# Latching.net
KiCad netlist of a schematic drawn in Altium Designer
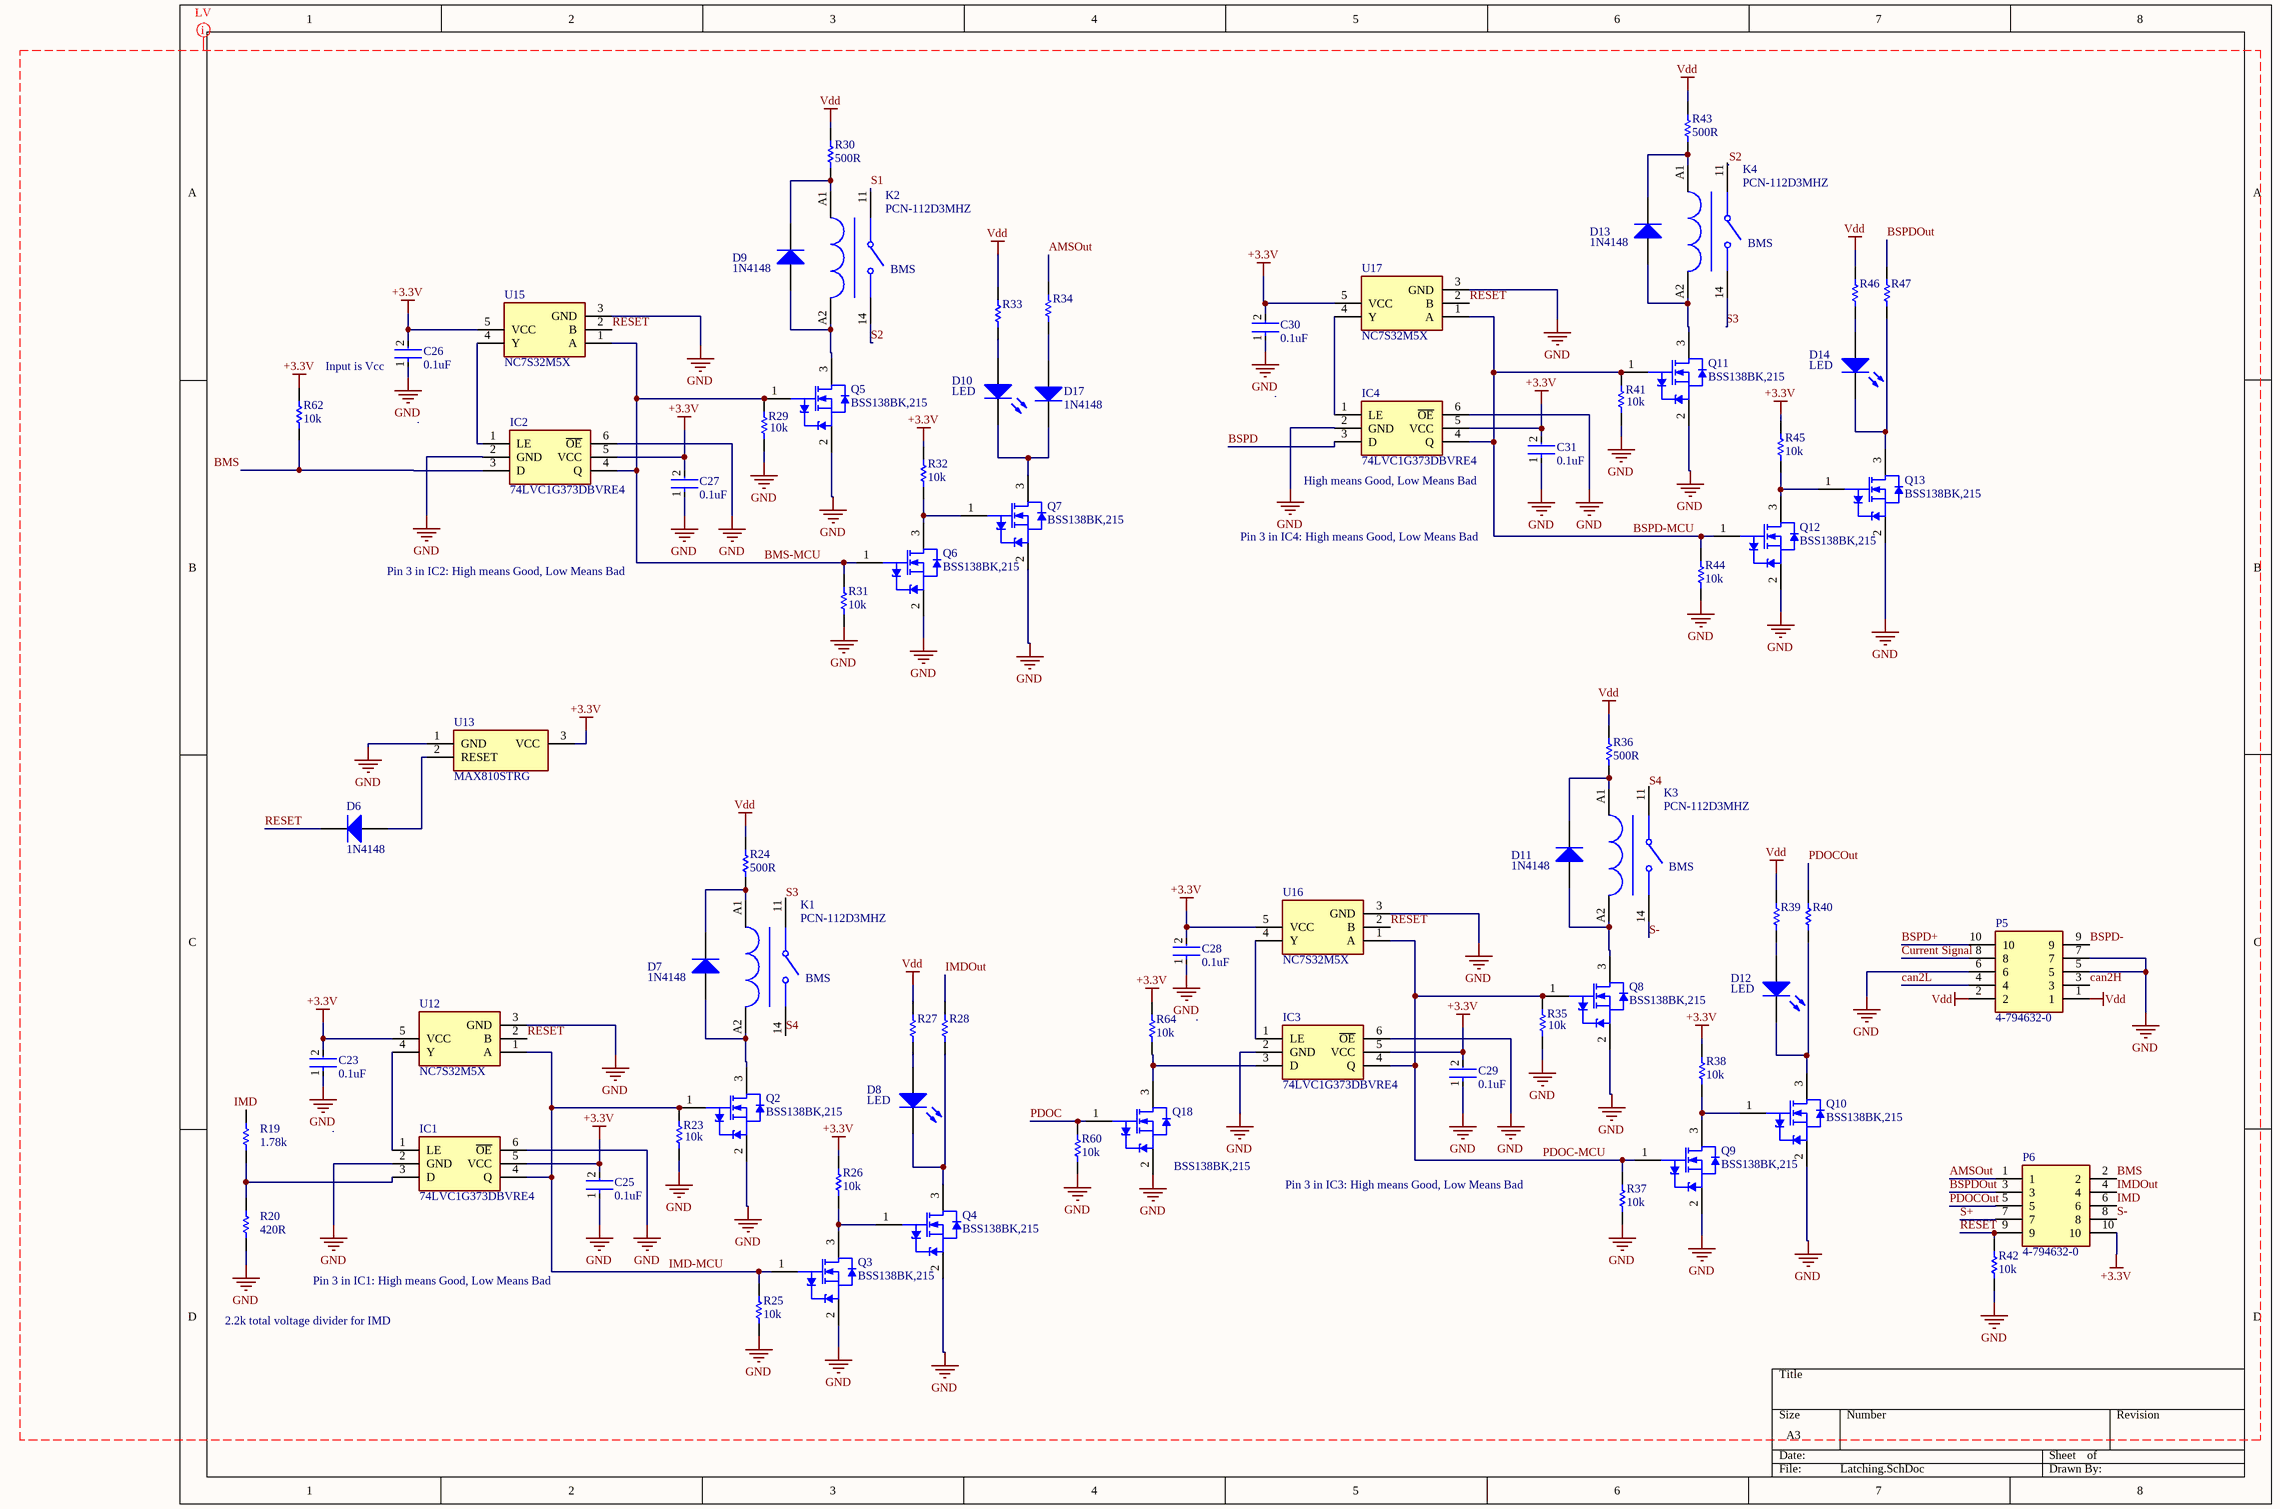
[diagram p0: Latching.SchDoc]

(export (version "E")
  (design (tool "Eeschema 10.0.6"))
  (components
    (comp (ref "C23")
      (value "0.1uF")
      (footprint "FP-C0603-CJ-MFG")
      (description "CAP CER 0.1UF 50V X7R 0603")
      (fields (field (name "MANUFACTURER PART NUMBER") "C0603X104K5RACTU") (field (name "VOLTAGE") "50V"))
      (libsource (lib "Altium Content Vault") (part "11868f565c42a9108669ba33697ecf6"))
    )
    (comp (ref "C25")
      (value "0.1uF")
      (footprint "FP-C0603-CJ-MFG")
      (description "CAP CER 0.1UF 50V X7R 0603")
      (fields (field (name "MANUFACTURER PART NUMBER") "C0603X104K5RACTU") (field (name "VOLTAGE") "50V"))
      (libsource (lib "Altium Content Vault") (part "11868f565c42a9108669ba33697ecf6"))
    )
    (comp (ref "C26")
      (value "0.1uF")
      (footprint "FP-C0603-CJ-MFG")
      (description "CAP CER 0.1UF 50V X7R 0603")
      (fields (field (name "MANUFACTURER PART NUMBER") "C0603X104K5RACTU") (field (name "VOLTAGE") "50V"))
      (libsource (lib "Altium Content Vault") (part "11868f565c42a9108669ba33697ecf6"))
    )
    (comp (ref "C27")
      (value "0.1uF")
      (footprint "FP-C0603-CJ-MFG")
      (description "CAP CER 0.1UF 50V X7R 0603")
      (fields (field (name "MANUFACTURER PART NUMBER") "C0603X104K5RACTU") (field (name "VOLTAGE") "50V"))
      (libsource (lib "Altium Content Vault") (part "11868f565c42a9108669ba33697ecf6"))
    )
    (comp (ref "C28")
      (value "0.1uF")
      (footprint "FP-C0603-CJ-MFG")
      (description "CAP CER 0.1UF 50V X7R 0603")
      (fields (field (name "MANUFACTURER PART NUMBER") "C0603X104K5RACTU") (field (name "VOLTAGE") "50V"))
      (libsource (lib "Altium Content Vault") (part "11868f565c42a9108669ba33697ecf6"))
    )
    (comp (ref "C29")
      (value "0.1uF")
      (footprint "FP-C0603-CJ-MFG")
      (description "CAP CER 0.1UF 50V X7R 0603")
      (fields (field (name "MANUFACTURER PART NUMBER") "C0603X104K5RACTU") (field (name "VOLTAGE") "50V"))
      (libsource (lib "Altium Content Vault") (part "11868f565c42a9108669ba33697ecf6"))
    )
    (comp (ref "C30")
      (value "0.1uF")
      (footprint "FP-C0603-CJ-MFG")
      (description "CAP CER 0.1UF 50V X7R 0603")
      (fields (field (name "MANUFACTURER PART NUMBER") "C0603X104K5RACTU") (field (name "VOLTAGE") "50V"))
      (libsource (lib "Altium Content Vault") (part "11868f565c42a9108669ba33697ecf6"))
    )
    (comp (ref "C31")
      (value "0.1uF")
      (footprint "FP-C0603-CJ-MFG")
      (description "CAP CER 0.1UF 50V X7R 0603")
      (fields (field (name "MANUFACTURER PART NUMBER") "C0603X104K5RACTU") (field (name "VOLTAGE") "50V"))
      (libsource (lib "Altium Content Vault") (part "11868f565c42a9108669ba33697ecf6"))
    )
    (comp (ref "D6")
      (value "1N4148")
      (footprint "DIOD-SOD123-2_V")
      (description "DIODE GEN PURP 100V 300MA SOD123")
      (fields (field (name "VOLTAGE") "100V"))
      (libsource (lib "Diodes") (part "1N4148W-7-F"))
    )
    (comp (ref "D7")
      (value "1N4148")
      (footprint "DIOD-SOD123-2_V")
      (description "DIODE GEN PURP 100V 300MA SOD123")
      (fields (field (name "VOLTAGE") "100V"))
      (libsource (lib "Diodes") (part "1N4148W-7-F"))
    )
    (comp (ref "D8")
      (value "LED")
      (footprint "1206_A")
      (description "WURTH ELEKTRONIK   150120SS75000   LED, 1206, SUP. RED, 60MCD, 630NM")
      (libsource (lib "LED") (part "150120SS75000"))
    )
    (comp (ref "D9")
      (value "1N4148")
      (footprint "DIOD-SOD123-2_V")
      (description "DIODE GEN PURP 100V 300MA SOD123")
      (fields (field (name "VOLTAGE") "100V"))
      (libsource (lib "Diodes") (part "1N4148W-7-F"))
    )
    (comp (ref "D10")
      (value "LED")
      (footprint "1206_A")
      (description "WURTH ELEKTRONIK   150120SS75000   LED, 1206, SUP. RED, 60MCD, 630NM")
      (libsource (lib "LED") (part "150120SS75000"))
    )
    (comp (ref "D11")
      (value "1N4148")
      (footprint "DIOD-SOD123-2_V")
      (description "DIODE GEN PURP 100V 300MA SOD123")
      (fields (field (name "VOLTAGE") "100V"))
      (libsource (lib "Diodes") (part "1N4148W-7-F"))
    )
    (comp (ref "D12")
      (value "LED")
      (footprint "1206_A")
      (description "WURTH ELEKTRONIK   150120SS75000   LED, 1206, SUP. RED, 60MCD, 630NM")
      (libsource (lib "LED") (part "150120SS75000"))
    )
    (comp (ref "D13")
      (value "1N4148")
      (footprint "DIOD-SOD123-2_V")
      (description "DIODE GEN PURP 100V 300MA SOD123")
      (fields (field (name "VOLTAGE") "100V"))
      (libsource (lib "Diodes") (part "1N4148W-7-F"))
    )
    (comp (ref "D14")
      (value "LED")
      (footprint "1206_A")
      (description "WURTH ELEKTRONIK   150120SS75000   LED, 1206, SUP. RED, 60MCD, 630NM")
      (libsource (lib "LED") (part "150120SS75000"))
    )
    (comp (ref "D17")
      (value "1N4148")
      (footprint "DIOD-SOD123-2_V")
      (description "DIODE GEN PURP 100V 300MA SOD123")
      (fields (field (name "VOLTAGE") "100V"))
      (libsource (lib "Diodes") (part "1N4148W-7-F"))
    )
    (comp (ref "IC1")
      (value "74LVC1G373DBVRE4")
      (footprint "SOT95P280X145-6N")
      (description "Integrated Circuit")
      (libsource (lib "*") (part "74LVC1G373DBVRE4"))
    )
    (comp (ref "IC2")
      (value "74LVC1G373DBVRE4")
      (footprint "SOT95P280X145-6N")
      (description "Integrated Circuit")
      (libsource (lib "*") (part "74LVC1G373DBVRE4"))
    )
    (comp (ref "IC3")
      (value "74LVC1G373DBVRE4")
      (footprint "SOT95P280X145-6N")
      (description "Integrated Circuit")
      (libsource (lib "*") (part "74LVC1G373DBVRE4"))
    )
    (comp (ref "IC4")
      (value "74LVC1G373DBVRE4")
      (footprint "SOT95P280X145-6N")
      (description "Integrated Circuit")
      (libsource (lib "*") (part "74LVC1G373DBVRE4"))
    )
    (comp (ref "K1")
      (value "PCN-112D3MHZ")
      (footprint "PCN-112D3MHZ")
      (description "Relay")
      (libsource (lib "SamacSys") (part "PCN-112D3MHZ"))
    )
    (comp (ref "K2")
      (value "PCN-112D3MHZ")
      (footprint "PCN-112D3MHZ")
      (description "Relay")
      (libsource (lib "SamacSys") (part "PCN-112D3MHZ"))
    )
    (comp (ref "K3")
      (value "PCN-112D3MHZ")
      (footprint "PCN-112D3MHZ")
      (description "Relay")
      (libsource (lib "SamacSys") (part "PCN-112D3MHZ"))
    )
    (comp (ref "K4")
      (value "PCN-112D3MHZ")
      (footprint "PCN-112D3MHZ")
      (description "Relay")
      (libsource (lib "SamacSys") (part "PCN-112D3MHZ"))
    )
    (comp (ref "P5")
      (value "4-794632-0")
      (footprint "SamacSys:SHDR10W82P300_2X5_1586X686X944P")
      (description "Connector")
      (fields (field (name "MOUSER PART NUMBER") "571-4-794632-0"))
      (libsource (lib "") (part "4-794632-0_1"))
    )
    (comp (ref "P6")
      (value "4-794632-0")
      (footprint "SamacSys:SHDR10W82P300_2X5_1586X686X944P")
      (description "Connector")
      (fields (field (name "MOUSER PART NUMBER") "571-4-794632-0"))
      (libsource (lib "SamacSys") (part "4-794632-0"))
    )
    (comp (ref "Q2")
      (value "BSS138BK,215")
      (footprint "NXP-SOT23_N")
      (description "N-Channel Trench MOSFET, 60 V, 0.36 A, -55 to 150 degC, 3-Pin SOT23, Tape and Reel")
      (fields (field (name "MANUFACTURER") "NXP Semiconductors"))
      (libsource (lib "Altium Content Vault") (part "NXP-NMOS-GSD-3"))
    )
    (comp (ref "Q3")
      (value "BSS138BK,215")
      (footprint "NXP-SOT23_N")
      (description "N-Channel Trench MOSFET, 60 V, 0.36 A, -55 to 150 degC, 3-Pin SOT23, Tape and Reel")
      (fields (field (name "MANUFACTURER") "NXP Semiconductors"))
      (libsource (lib "Altium Content Vault") (part "NXP-NMOS-GSD-3"))
    )
    (comp (ref "Q4")
      (value "BSS138BK,215")
      (footprint "NXP-SOT23_N")
      (description "N-Channel Trench MOSFET, 60 V, 0.36 A, -55 to 150 degC, 3-Pin SOT23, Tape and Reel")
      (fields (field (name "MANUFACTURER") "NXP Semiconductors"))
      (libsource (lib "Altium Content Vault") (part "NXP-NMOS-GSD-3"))
    )
    (comp (ref "Q5")
      (value "BSS138BK,215")
      (footprint "NXP-SOT23_N")
      (description "N-Channel Trench MOSFET, 60 V, 0.36 A, -55 to 150 degC, 3-Pin SOT23, Tape and Reel")
      (fields (field (name "MANUFACTURER") "NXP Semiconductors"))
      (libsource (lib "Altium Content Vault") (part "NXP-NMOS-GSD-3"))
    )
    (comp (ref "Q6")
      (value "BSS138BK,215")
      (footprint "NXP-SOT23_N")
      (description "N-Channel Trench MOSFET, 60 V, 0.36 A, -55 to 150 degC, 3-Pin SOT23, Tape and Reel")
      (fields (field (name "MANUFACTURER") "NXP Semiconductors"))
      (libsource (lib "Altium Content Vault") (part "NXP-NMOS-GSD-3"))
    )
    (comp (ref "Q7")
      (value "BSS138BK,215")
      (footprint "NXP-SOT23_N")
      (description "N-Channel Trench MOSFET, 60 V, 0.36 A, -55 to 150 degC, 3-Pin SOT23, Tape and Reel")
      (fields (field (name "MANUFACTURER") "NXP Semiconductors"))
      (libsource (lib "Altium Content Vault") (part "NXP-NMOS-GSD-3"))
    )
    (comp (ref "Q8")
      (value "BSS138BK,215")
      (footprint "NXP-SOT23_N")
      (description "N-Channel Trench MOSFET, 60 V, 0.36 A, -55 to 150 degC, 3-Pin SOT23, Tape and Reel")
      (fields (field (name "MANUFACTURER") "NXP Semiconductors"))
      (libsource (lib "Altium Content Vault") (part "NXP-NMOS-GSD-3"))
    )
    (comp (ref "Q9")
      (value "BSS138BK,215")
      (footprint "NXP-SOT23_N")
      (description "N-Channel Trench MOSFET, 60 V, 0.36 A, -55 to 150 degC, 3-Pin SOT23, Tape and Reel")
      (fields (field (name "MANUFACTURER") "NXP Semiconductors"))
      (libsource (lib "Altium Content Vault") (part "NXP-NMOS-GSD-3"))
    )
    (comp (ref "Q10")
      (value "BSS138BK,215")
      (footprint "NXP-SOT23_N")
      (description "N-Channel Trench MOSFET, 60 V, 0.36 A, -55 to 150 degC, 3-Pin SOT23, Tape and Reel")
      (fields (field (name "MANUFACTURER") "NXP Semiconductors"))
      (libsource (lib "Altium Content Vault") (part "NXP-NMOS-GSD-3"))
    )
    (comp (ref "Q11")
      (value "BSS138BK,215")
      (footprint "NXP-SOT23_N")
      (description "N-Channel Trench MOSFET, 60 V, 0.36 A, -55 to 150 degC, 3-Pin SOT23, Tape and Reel")
      (fields (field (name "MANUFACTURER") "NXP Semiconductors"))
      (libsource (lib "Altium Content Vault") (part "NXP-NMOS-GSD-3"))
    )
    (comp (ref "Q12")
      (value "BSS138BK,215")
      (footprint "NXP-SOT23_N")
      (description "N-Channel Trench MOSFET, 60 V, 0.36 A, -55 to 150 degC, 3-Pin SOT23, Tape and Reel")
      (fields (field (name "MANUFACTURER") "NXP Semiconductors"))
      (libsource (lib "Altium Content Vault") (part "NXP-NMOS-GSD-3"))
    )
    (comp (ref "Q13")
      (value "BSS138BK,215")
      (footprint "NXP-SOT23_N")
      (description "N-Channel Trench MOSFET, 60 V, 0.36 A, -55 to 150 degC, 3-Pin SOT23, Tape and Reel")
      (fields (field (name "MANUFACTURER") "NXP Semiconductors"))
      (libsource (lib "Altium Content Vault") (part "NXP-NMOS-GSD-3"))
    )
    (comp (ref "Q18")
      (value "BSS138BK,215")
      (footprint "NXP-SOT23_N")
      (description "N-Channel Trench MOSFET, 60 V, 0.36 A, -55 to 150 degC, 3-Pin SOT23, Tape and Reel")
      (fields (field (name "MANUFACTURER") "NXP Semiconductors"))
      (libsource (lib "Altium Content Vault") (part "NXP-NMOS-GSD-3"))
    )
    (comp (ref "R19")
      (value "1.78k")
      (footprint "RESC1608X55N")
      (description "679-0260")
      (fields (field (name "Comment") "Res1") (field (name "PUBLISHER") "Altium Limited"))
      (libsource (lib "Miscellaneous Devices") (part "Res1"))
    )
    (comp (ref "R20")
      (value "420R")
      (footprint "RESC1608X55N")
      (description "679-0260")
      (fields (field (name "Comment") "Res1") (field (name "PUBLISHER") "Altium Limited"))
      (libsource (lib "Miscellaneous Devices") (part "Res1"))
    )
    (comp (ref "R23")
      (value "10k")
      (footprint "RESC1608X55N")
      (description "10k E0805 1% 1/8W")
      (fields (field (name "TOLERANCE") "5%"))
      (libsource (lib "Resistors") (part "RC0805JR-0710KL"))
    )
    (comp (ref "R24")
      (value "500R")
      (footprint "RESC1608X55N")
      (description "10k E0805 1% 1/8W")
      (fields (field (name "TOLERANCE") "5%"))
      (libsource (lib "Resistors") (part "RC0805JR-0710KL"))
    )
    (comp (ref "R25")
      (value "10k")
      (footprint "RESC1608X55N")
      (description "10k E0805 1% 1/8W")
      (fields (field (name "TOLERANCE") "5%"))
      (libsource (lib "Resistors") (part "RC0805JR-0710KL"))
    )
    (comp (ref "R26")
      (value "10k")
      (footprint "RESC1608X55N")
      (description "10k E0805 1% 1/8W")
      (fields (field (name "TOLERANCE") "5%"))
      (libsource (lib "Resistors") (part "RC0805JR-0710KL"))
    )
    (comp (ref "R27")
      (value "CRCW2512649RFKEG")
      (footprint "Resistor__E2512")
      (description "RES SMD 649 OHM 1% 1W 2512")
      (fields (field (name "TOLERANCE") "1%"))
      (libsource (lib "Resistors") (part "CRCW2512649RFKEG"))
    )
    (comp (ref "R28")
      (value "CRCW2512649RFKEG")
      (footprint "Resistor__E2512")
      (description "RES SMD 649 OHM 1% 1W 2512")
      (fields (field (name "TOLERANCE") "1%"))
      (libsource (lib "Resistors") (part "CRCW2512649RFKEG"))
    )
    (comp (ref "R29")
      (value "10k")
      (footprint "RESC1608X55N")
      (description "10k E0805 1% 1/8W")
      (fields (field (name "TOLERANCE") "5%"))
      (libsource (lib "Resistors") (part "RC0805JR-0710KL"))
    )
    (comp (ref "R30")
      (value "500R")
      (footprint "RESC1608X55N")
      (description "10k E0805 1% 1/8W")
      (fields (field (name "TOLERANCE") "5%"))
      (libsource (lib "Resistors") (part "RC0805JR-0710KL"))
    )
    (comp (ref "R31")
      (value "10k")
      (footprint "RESC1608X55N")
      (description "10k E0805 1% 1/8W")
      (fields (field (name "TOLERANCE") "5%"))
      (libsource (lib "Resistors") (part "RC0805JR-0710KL"))
    )
    (comp (ref "R32")
      (value "10k")
      (footprint "RESC1608X55N")
      (description "10k E0805 1% 1/8W")
      (fields (field (name "TOLERANCE") "5%"))
      (libsource (lib "Resistors") (part "RC0805JR-0710KL"))
    )
    (comp (ref "R33")
      (value "CRCW2512649RFKEG")
      (footprint "Resistor__E2512")
      (description "RES SMD 649 OHM 1% 1W 2512")
      (fields (field (name "TOLERANCE") "1%"))
      (libsource (lib "Resistors") (part "CRCW2512649RFKEG"))
    )
    (comp (ref "R34")
      (value "CRCW2512649RFKEG")
      (footprint "Resistor__E2512")
      (description "RES SMD 649 OHM 1% 1W 2512")
      (fields (field (name "TOLERANCE") "1%"))
      (libsource (lib "Resistors") (part "CRCW2512649RFKEG"))
    )
    (comp (ref "R35")
      (value "10k")
      (footprint "RESC1608X55N")
      (description "10k E0805 1% 1/8W")
      (fields (field (name "TOLERANCE") "5%"))
      (libsource (lib "Resistors") (part "RC0805JR-0710KL"))
    )
    (comp (ref "R36")
      (value "500R")
      (footprint "RESC1608X55N")
      (description "10k E0805 1% 1/8W")
      (fields (field (name "TOLERANCE") "5%"))
      (libsource (lib "Resistors") (part "RC0805JR-0710KL"))
    )
    (comp (ref "R37")
      (value "10k")
      (footprint "RESC1608X55N")
      (description "10k E0805 1% 1/8W")
      (fields (field (name "TOLERANCE") "5%"))
      (libsource (lib "Resistors") (part "RC0805JR-0710KL"))
    )
    (comp (ref "R38")
      (value "10k")
      (footprint "RESC1608X55N")
      (description "10k E0805 1% 1/8W")
      (fields (field (name "TOLERANCE") "5%"))
      (libsource (lib "Resistors") (part "RC0805JR-0710KL"))
    )
    (comp (ref "R39")
      (value "CRCW2512649RFKEG")
      (footprint "Resistor__E2512")
      (description "RES SMD 649 OHM 1% 1W 2512")
      (fields (field (name "TOLERANCE") "1%"))
      (libsource (lib "Resistors") (part "CRCW2512649RFKEG"))
    )
    (comp (ref "R40")
      (value "CRCW2512649RFKEG")
      (footprint "Resistor__E2512")
      (description "RES SMD 649 OHM 1% 1W 2512")
      (fields (field (name "TOLERANCE") "1%"))
      (libsource (lib "Resistors") (part "CRCW2512649RFKEG"))
    )
    (comp (ref "R41")
      (value "10k")
      (footprint "RESC1608X55N")
      (description "10k E0805 1% 1/8W")
      (fields (field (name "TOLERANCE") "5%"))
      (libsource (lib "Resistors") (part "RC0805JR-0710KL"))
    )
    (comp (ref "R42")
      (value "10k")
      (footprint "RESC1608X55N")
      (description "10k E0805 1% 1/8W")
      (fields (field (name "TOLERANCE") "5%"))
      (libsource (lib "Resistors") (part "RC0805JR-0710KL"))
    )
    (comp (ref "R43")
      (value "500R")
      (footprint "RESC1608X55N")
      (description "10k E0805 1% 1/8W")
      (fields (field (name "TOLERANCE") "5%"))
      (libsource (lib "Resistors") (part "RC0805JR-0710KL"))
    )
    (comp (ref "R44")
      (value "10k")
      (footprint "RESC1608X55N")
      (description "10k E0805 1% 1/8W")
      (fields (field (name "TOLERANCE") "5%"))
      (libsource (lib "Resistors") (part "RC0805JR-0710KL"))
    )
    (comp (ref "R45")
      (value "10k")
      (footprint "RESC1608X55N")
      (description "10k E0805 1% 1/8W")
      (fields (field (name "TOLERANCE") "5%"))
      (libsource (lib "Resistors") (part "RC0805JR-0710KL"))
    )
    (comp (ref "R46")
      (value "CRCW2512649RFKEG")
      (footprint "Resistor__E2512")
      (description "RES SMD 649 OHM 1% 1W 2512")
      (fields (field (name "TOLERANCE") "1%"))
      (libsource (lib "Resistors") (part "CRCW2512649RFKEG"))
    )
    (comp (ref "R47")
      (value "CRCW2512649RFKEG")
      (footprint "Resistor__E2512")
      (description "RES SMD 649 OHM 1% 1W 2512")
      (fields (field (name "TOLERANCE") "1%"))
      (libsource (lib "Resistors") (part "CRCW2512649RFKEG"))
    )
    (comp (ref "R60")
      (value "10k")
      (footprint "RESC1608X55N")
      (description "10k E0805 1% 1/8W")
      (fields (field (name "TOLERANCE") "5%"))
      (libsource (lib "Resistors") (part "RC0805JR-0710KL"))
    )
    (comp (ref "R62")
      (value "10k")
      (footprint "RESC1608X55N")
      (description "10k E0805 1% 1/8W")
      (fields (field (name "TOLERANCE") "5%"))
      (libsource (lib "Resistors") (part "RC0805JR-0710KL"))
    )
    (comp (ref "R64")
      (value "10k")
      (footprint "RESC1608X55N")
      (description "10k E0805 1% 1/8W")
      (fields (field (name "TOLERANCE") "5%"))
      (libsource (lib "Resistors") (part "RC0805JR-0710KL"))
    )
    (comp (ref "U12")
      (value "NC7S32M5X")
      (footprint "SOT95P275X110-5N")
      (description "OR GATEEEE")
      (libsource (lib "SamacSys") (part "NC7S32M5X"))
    )
    (comp (ref "U13")
      (value "MAX810STRG")
      (footprint "SOT96P237X111-3N")
      (description "Integrated Circuit")
      (fields (field (name "MANUFACTURER_PART_NUMBER") "MAX810TTRG"))
      (libsource (lib "SamacSys") (part "MAX810TTRG"))
    )
    (comp (ref "U15")
      (value "NC7S32M5X")
      (footprint "SOT95P275X110-5N")
      (description "OR GATEEEE")
      (libsource (lib "SamacSys") (part "NC7S32M5X"))
    )
    (comp (ref "U16")
      (value "NC7S32M5X")
      (footprint "SOT95P275X110-5N")
      (description "OR GATEEEE")
      (libsource (lib "SamacSys") (part "NC7S32M5X"))
    )
    (comp (ref "U17")
      (value "NC7S32M5X")
      (footprint "SOT95P275X110-5N")
      (description "OR GATEEEE")
      (libsource (lib "SamacSys") (part "NC7S32M5X"))
    )
  )
  (nets
    (net (code "1") (name "+3.3V") (class "Default")
      (node (ref "C23") (pin "2") (pinfunction "2_2") (pintype "passive"))
      (node (ref "C25") (pin "2") (pinfunction "2_2") (pintype "passive"))
      (node (ref "C26") (pin "2") (pinfunction "2_2") (pintype "passive"))
      (node (ref "C27") (pin "2") (pinfunction "2_2") (pintype "passive"))
      (node (ref "C28") (pin "2") (pinfunction "2_2") (pintype "passive"))
      (node (ref "C29") (pin "2") (pinfunction "2_2") (pintype "passive"))
      (node (ref "C30") (pin "2") (pinfunction "2_2") (pintype "passive"))
      (node (ref "C31") (pin "2") (pinfunction "2_2") (pintype "passive"))
      (node (ref "IC1") (pin "5") (pinfunction "VCC_5") (pintype "passive"))
      (node (ref "IC2") (pin "5") (pinfunction "VCC_5") (pintype "passive"))
      (node (ref "IC3") (pin "5") (pinfunction "VCC_5") (pintype "passive"))
      (node (ref "IC4") (pin "5") (pinfunction "VCC_5") (pintype "passive"))
      (node (ref "P6") (pin "10") (pinfunction "10_10") (pintype "passive"))
      (node (ref "R26") (pin "2") (pinfunction "2_2") (pintype "passive"))
      (node (ref "R32") (pin "2") (pinfunction "2_2") (pintype "passive"))
      (node (ref "R38") (pin "2") (pinfunction "2_2") (pintype "passive"))
      (node (ref "R45") (pin "2") (pinfunction "2_2") (pintype "passive"))
      (node (ref "R62") (pin "2") (pinfunction "2_2") (pintype "passive"))
      (node (ref "R64") (pin "2") (pinfunction "2_2") (pintype "passive"))
      (node (ref "U12") (pin "5") (pinfunction "VCC_5") (pintype "passive"))
      (node (ref "U13") (pin "3") (pinfunction "VCC_3") (pintype "power_in"))
      (node (ref "U15") (pin "5") (pinfunction "VCC_5") (pintype "passive"))
      (node (ref "U16") (pin "5") (pinfunction "VCC_5") (pintype "passive"))
      (node (ref "U17") (pin "5") (pinfunction "VCC_5") (pintype "passive"))
    )
    (net (code "2") (name "/AMSOut") (class "Default")
      (node (ref "P6") (pin "1") (pinfunction "1_1") (pintype "passive"))
      (node (ref "R34") (pin "2") (pinfunction "2_2") (pintype "passive"))
    )
    (net (code "3") (name "/BMS") (class "Default")
      (node (ref "IC2") (pin "3") (pinfunction "D_3") (pintype "passive"))
      (node (ref "P6") (pin "2") (pinfunction "2_2") (pintype "passive"))
      (node (ref "R62") (pin "1") (pinfunction "1_1") (pintype "passive"))
    )
    (net (code "4") (name "/BMS-MCU") (class "Default")
      (node (ref "IC2") (pin "4") (pinfunction "Q_4") (pintype "passive"))
      (node (ref "Q5") (pin "1") (pinfunction "G_1") (pintype "passive"))
      (node (ref "Q6") (pin "1") (pinfunction "G_1") (pintype "passive"))
      (node (ref "R29") (pin "2") (pinfunction "2_2") (pintype "passive"))
      (node (ref "R31") (pin "2") (pinfunction "2_2") (pintype "passive"))
      (node (ref "U15") (pin "1") (pinfunction "A_1") (pintype "passive"))
    )
    (net (code "5") (name "/BSPD") (class "Default")
      (node (ref "IC4") (pin "3") (pinfunction "D_3") (pintype "passive"))
    )
    (net (code "6") (name "/BSPD+") (class "Default")
      (node (ref "P5") (pin "10") (pinfunction "10_10") (pintype "passive"))
    )
    (net (code "7") (name "/BSPD-") (class "Default")
      (node (ref "P5") (pin "9") (pinfunction "9_9") (pintype "passive"))
    )
    (net (code "8") (name "/BSPD-MCU") (class "Default")
      (node (ref "IC4") (pin "4") (pinfunction "Q_4") (pintype "passive"))
      (node (ref "Q11") (pin "1") (pinfunction "G_1") (pintype "passive"))
      (node (ref "Q12") (pin "1") (pinfunction "G_1") (pintype "passive"))
      (node (ref "R41") (pin "2") (pinfunction "2_2") (pintype "passive"))
      (node (ref "R44") (pin "2") (pinfunction "2_2") (pintype "passive"))
      (node (ref "U17") (pin "1") (pinfunction "A_1") (pintype "passive"))
    )
    (net (code "9") (name "/BSPDOut") (class "Default")
      (node (ref "P6") (pin "3") (pinfunction "3_3") (pintype "passive"))
      (node (ref "R47") (pin "2") (pinfunction "2_2") (pintype "passive"))
    )
    (net (code "10") (name "/Current Signal") (class "Default")
      (node (ref "P5") (pin "8") (pinfunction "8_8") (pintype "passive"))
    )
    (net (code "11") (name "/IMD") (class "Default")
      (node (ref "P6") (pin "6") (pinfunction "6_6") (pintype "passive"))
      (node (ref "R19") (pin "2") (pinfunction "2_2") (pintype "passive"))
    )
    (net (code "12") (name "/IMD-MCU") (class "Default")
      (node (ref "IC1") (pin "4") (pinfunction "Q_4") (pintype "passive"))
      (node (ref "Q2") (pin "1") (pinfunction "G_1") (pintype "passive"))
      (node (ref "Q3") (pin "1") (pinfunction "G_1") (pintype "passive"))
      (node (ref "R23") (pin "2") (pinfunction "2_2") (pintype "passive"))
      (node (ref "R25") (pin "2") (pinfunction "2_2") (pintype "passive"))
      (node (ref "U12") (pin "1") (pinfunction "A_1") (pintype "passive"))
    )
    (net (code "13") (name "/IMDOut") (class "Default")
      (node (ref "P6") (pin "4") (pinfunction "4_4") (pintype "passive"))
      (node (ref "R28") (pin "2") (pinfunction "2_2") (pintype "passive"))
    )
    (net (code "14") (name "/PDOC") (class "Default")
      (node (ref "Q18") (pin "1") (pinfunction "G_1") (pintype "passive"))
      (node (ref "R60") (pin "2") (pinfunction "2_2") (pintype "passive"))
    )
    (net (code "15") (name "/PDOC-MCU") (class "Default")
      (node (ref "IC3") (pin "4") (pinfunction "Q_4") (pintype "passive"))
      (node (ref "Q8") (pin "1") (pinfunction "G_1") (pintype "passive"))
      (node (ref "Q9") (pin "1") (pinfunction "G_1") (pintype "passive"))
      (node (ref "R35") (pin "2") (pinfunction "2_2") (pintype "passive"))
      (node (ref "R37") (pin "2") (pinfunction "2_2") (pintype "passive"))
      (node (ref "U16") (pin "1") (pinfunction "A_1") (pintype "passive"))
    )
    (net (code "16") (name "/PDOCOut") (class "Default")
      (node (ref "P6") (pin "5") (pinfunction "5_5") (pintype "passive"))
      (node (ref "R40") (pin "2") (pinfunction "2_2") (pintype "passive"))
    )
    (net (code "17") (name "/RESET") (class "Default")
      (node (ref "D6") (pin "2") (pinfunction "K_2") (pintype "passive"))
      (node (ref "P6") (pin "9") (pinfunction "9_9") (pintype "passive"))
      (node (ref "R42") (pin "2") (pinfunction "2_2") (pintype "passive"))
      (node (ref "U12") (pin "2") (pinfunction "B_2") (pintype "passive"))
      (node (ref "U15") (pin "2") (pinfunction "B_2") (pintype "passive"))
      (node (ref "U16") (pin "2") (pinfunction "B_2") (pintype "passive"))
      (node (ref "U17") (pin "2") (pinfunction "B_2") (pintype "passive"))
    )
    (net (code "18") (name "/S+") (class "Default")
      (node (ref "P6") (pin "7") (pinfunction "7_7") (pintype "passive"))
    )
    (net (code "19") (name "/S-") (class "Default")
      (node (ref "K3") (pin "14") (pintype "passive"))
      (node (ref "P6") (pin "8") (pinfunction "8_8") (pintype "passive"))
    )
    (net (code "20") (name "/S1") (class "Default") (node (ref "K2") (pin "11") (pintype "passive")))
    (net (code "21") (name "/S2") (class "Default")
      (node (ref "K2") (pin "14") (pintype "passive"))
      (node (ref "K4") (pin "11") (pintype "passive"))
    )
    (net (code "22") (name "/S3") (class "Default")
      (node (ref "K1") (pin "11") (pintype "passive"))
      (node (ref "K4") (pin "14") (pintype "passive"))
    )
    (net (code "23") (name "/S4") (class "Default")
      (node (ref "K1") (pin "14") (pintype "passive"))
      (node (ref "K3") (pin "11") (pintype "passive"))
    )
    (net (code "24") (name "/can2H") (class "Default")
      (node (ref "P5") (pin "3") (pinfunction "3_3") (pintype "passive"))
    )
    (net (code "25") (name "/can2L") (class "Default")
      (node (ref "P5") (pin "4") (pinfunction "4_4") (pintype "passive"))
    )
    (net (code "26") (name "GND") (class "Default")
      (node (ref "C23") (pin "1") (pinfunction "1_1") (pintype "passive"))
      (node (ref "C25") (pin "1") (pinfunction "1_1") (pintype "passive"))
      (node (ref "C26") (pin "1") (pinfunction "1_1") (pintype "passive"))
      (node (ref "C27") (pin "1") (pinfunction "1_1") (pintype "passive"))
      (node (ref "C28") (pin "1") (pinfunction "1_1") (pintype "passive"))
      (node (ref "C29") (pin "1") (pinfunction "1_1") (pintype "passive"))
      (node (ref "C30") (pin "1") (pinfunction "1_1") (pintype "passive"))
      (node (ref "C31") (pin "1") (pinfunction "1_1") (pintype "passive"))
      (node (ref "IC1") (pin "2") (pinfunction "GND_2") (pintype "passive"))
      (node (ref "IC1") (pin "6") (pinfunction "~{OE}_6") (pintype "passive"))
      (node (ref "IC2") (pin "2") (pinfunction "GND_2") (pintype "passive"))
      (node (ref "IC2") (pin "6") (pinfunction "~{OE}_6") (pintype "passive"))
      (node (ref "IC3") (pin "2") (pinfunction "GND_2") (pintype "passive"))
      (node (ref "IC3") (pin "6") (pinfunction "~{OE}_6") (pintype "passive"))
      (node (ref "IC4") (pin "2") (pinfunction "GND_2") (pintype "passive"))
      (node (ref "IC4") (pin "6") (pinfunction "~{OE}_6") (pintype "passive"))
      (node (ref "P5") (pin "5") (pinfunction "5_5") (pintype "passive"))
      (node (ref "P5") (pin "6") (pinfunction "6_6") (pintype "passive"))
      (node (ref "P5") (pin "7") (pinfunction "7_7") (pintype "passive"))
      (node (ref "Q10") (pin "2") (pinfunction "S_2") (pintype "passive"))
      (node (ref "Q11") (pin "2") (pinfunction "S_2") (pintype "passive"))
      (node (ref "Q12") (pin "2") (pinfunction "S_2") (pintype "passive"))
      (node (ref "Q13") (pin "2") (pinfunction "S_2") (pintype "passive"))
      (node (ref "Q18") (pin "2") (pinfunction "S_2") (pintype "passive"))
      (node (ref "Q2") (pin "2") (pinfunction "S_2") (pintype "passive"))
      (node (ref "Q3") (pin "2") (pinfunction "S_2") (pintype "passive"))
      (node (ref "Q4") (pin "2") (pinfunction "S_2") (pintype "passive"))
      (node (ref "Q5") (pin "2") (pinfunction "S_2") (pintype "passive"))
      (node (ref "Q6") (pin "2") (pinfunction "S_2") (pintype "passive"))
      (node (ref "Q7") (pin "2") (pinfunction "S_2") (pintype "passive"))
      (node (ref "Q8") (pin "2") (pinfunction "S_2") (pintype "passive"))
      (node (ref "Q9") (pin "2") (pinfunction "S_2") (pintype "passive"))
      (node (ref "R20") (pin "1") (pinfunction "1_1") (pintype "passive"))
      (node (ref "R23") (pin "1") (pinfunction "1_1") (pintype "passive"))
      (node (ref "R25") (pin "1") (pinfunction "1_1") (pintype "passive"))
      (node (ref "R29") (pin "1") (pinfunction "1_1") (pintype "passive"))
      (node (ref "R31") (pin "1") (pinfunction "1_1") (pintype "passive"))
      (node (ref "R35") (pin "1") (pinfunction "1_1") (pintype "passive"))
      (node (ref "R37") (pin "1") (pinfunction "1_1") (pintype "passive"))
      (node (ref "R41") (pin "1") (pinfunction "1_1") (pintype "passive"))
      (node (ref "R42") (pin "1") (pinfunction "1_1") (pintype "passive"))
      (node (ref "R44") (pin "1") (pinfunction "1_1") (pintype "passive"))
      (node (ref "R60") (pin "1") (pinfunction "1_1") (pintype "passive"))
      (node (ref "U12") (pin "3") (pinfunction "GND_3") (pintype "passive"))
      (node (ref "U13") (pin "1") (pinfunction "GND_1") (pintype "power_in"))
      (node (ref "U15") (pin "3") (pinfunction "GND_3") (pintype "passive"))
      (node (ref "U16") (pin "3") (pinfunction "GND_3") (pintype "passive"))
      (node (ref "U17") (pin "3") (pinfunction "GND_3") (pintype "passive"))
    )
    (net (code "27") (name "Net-(D6-A)") (class "Default")
      (node (ref "D6") (pin "1") (pinfunction "A_1") (pintype "passive"))
      (node (ref "U13") (pin "2") (pinfunction "RESET_2") (pintype "passive"))
    )
    (net (code "28") (name "Net-(D7-A)") (class "Default")
      (node (ref "D7") (pin "1") (pinfunction "A_1") (pintype "passive"))
      (node (ref "K1") (pin "A2") (pintype "passive"))
      (node (ref "Q2") (pin "3") (pinfunction "D_3") (pintype "passive"))
    )
    (net (code "29") (name "Net-(D7-K)") (class "Default")
      (node (ref "D7") (pin "2") (pinfunction "K_2") (pintype "passive"))
      (node (ref "K1") (pin "A1") (pintype "passive"))
      (node (ref "R24") (pin "1") (pinfunction "1_1") (pintype "passive"))
    )
    (net (code "30") (name "Net-(D8-A)") (class "Default")
      (node (ref "D8") (pin "2") (pinfunction "A_2") (pintype "passive"))
      (node (ref "R27") (pin "1") (pinfunction "1_1") (pintype "passive"))
    )
    (net (code "31") (name "Net-(D8-K)") (class "Default")
      (node (ref "D8") (pin "1") (pinfunction "K_1") (pintype "passive"))
      (node (ref "Q4") (pin "3") (pinfunction "D_3") (pintype "passive"))
      (node (ref "R28") (pin "1") (pinfunction "1_1") (pintype "passive"))
    )
    (net (code "32") (name "Net-(D9-A)") (class "Default")
      (node (ref "D9") (pin "1") (pinfunction "A_1") (pintype "passive"))
      (node (ref "K2") (pin "A2") (pintype "passive"))
      (node (ref "Q5") (pin "3") (pinfunction "D_3") (pintype "passive"))
    )
    (net (code "33") (name "Net-(D9-K)") (class "Default")
      (node (ref "D9") (pin "2") (pinfunction "K_2") (pintype "passive"))
      (node (ref "K2") (pin "A1") (pintype "passive"))
      (node (ref "R30") (pin "1") (pinfunction "1_1") (pintype "passive"))
    )
    (net (code "34") (name "Net-(D10-A)") (class "Default")
      (node (ref "D10") (pin "2") (pinfunction "A_2") (pintype "passive"))
      (node (ref "R33") (pin "1") (pinfunction "1_1") (pintype "passive"))
    )
    (net (code "35") (name "Net-(D10-K)") (class "Default")
      (node (ref "D10") (pin "1") (pinfunction "K_1") (pintype "passive"))
      (node (ref "D17") (pin "2") (pinfunction "K_2") (pintype "passive"))
      (node (ref "Q7") (pin "3") (pinfunction "D_3") (pintype "passive"))
    )
    (net (code "36") (name "Net-(D11-A)") (class "Default")
      (node (ref "D11") (pin "1") (pinfunction "A_1") (pintype "passive"))
      (node (ref "K3") (pin "A2") (pintype "passive"))
      (node (ref "Q8") (pin "3") (pinfunction "D_3") (pintype "passive"))
    )
    (net (code "37") (name "Net-(D11-K)") (class "Default")
      (node (ref "D11") (pin "2") (pinfunction "K_2") (pintype "passive"))
      (node (ref "K3") (pin "A1") (pintype "passive"))
      (node (ref "R36") (pin "1") (pinfunction "1_1") (pintype "passive"))
    )
    (net (code "38") (name "Net-(D12-A)") (class "Default")
      (node (ref "D12") (pin "2") (pinfunction "A_2") (pintype "passive"))
      (node (ref "R39") (pin "1") (pinfunction "1_1") (pintype "passive"))
    )
    (net (code "39") (name "Net-(D12-K)") (class "Default")
      (node (ref "D12") (pin "1") (pinfunction "K_1") (pintype "passive"))
      (node (ref "Q10") (pin "3") (pinfunction "D_3") (pintype "passive"))
      (node (ref "R40") (pin "1") (pinfunction "1_1") (pintype "passive"))
    )
    (net (code "40") (name "Net-(D13-A)") (class "Default")
      (node (ref "D13") (pin "1") (pinfunction "A_1") (pintype "passive"))
      (node (ref "K4") (pin "A2") (pintype "passive"))
      (node (ref "Q11") (pin "3") (pinfunction "D_3") (pintype "passive"))
    )
    (net (code "41") (name "Net-(D13-K)") (class "Default")
      (node (ref "D13") (pin "2") (pinfunction "K_2") (pintype "passive"))
      (node (ref "K4") (pin "A1") (pintype "passive"))
      (node (ref "R43") (pin "1") (pinfunction "1_1") (pintype "passive"))
    )
    (net (code "42") (name "Net-(D14-A)") (class "Default")
      (node (ref "D14") (pin "2") (pinfunction "A_2") (pintype "passive"))
      (node (ref "R46") (pin "1") (pinfunction "1_1") (pintype "passive"))
    )
    (net (code "43") (name "Net-(D14-K)") (class "Default")
      (node (ref "D14") (pin "1") (pinfunction "K_1") (pintype "passive"))
      (node (ref "Q13") (pin "3") (pinfunction "D_3") (pintype "passive"))
      (node (ref "R47") (pin "1") (pinfunction "1_1") (pintype "passive"))
    )
    (net (code "44") (name "Net-(D17-A)") (class "Default")
      (node (ref "D17") (pin "1") (pinfunction "A_1") (pintype "passive"))
      (node (ref "R34") (pin "1") (pinfunction "1_1") (pintype "passive"))
    )
    (net (code "45") (name "Net-(IC1-D)") (class "Default")
      (node (ref "IC1") (pin "3") (pinfunction "D_3") (pintype "passive"))
      (node (ref "R19") (pin "1") (pinfunction "1_1") (pintype "passive"))
      (node (ref "R20") (pin "2") (pinfunction "2_2") (pintype "passive"))
    )
    (net (code "46") (name "Net-(IC1-LE)") (class "Default")
      (node (ref "IC1") (pin "1") (pinfunction "LE_1") (pintype "passive"))
      (node (ref "U12") (pin "4") (pinfunction "Y_4") (pintype "passive"))
    )
    (net (code "47") (name "Net-(IC2-LE)") (class "Default")
      (node (ref "IC2") (pin "1") (pinfunction "LE_1") (pintype "passive"))
      (node (ref "U15") (pin "4") (pinfunction "Y_4") (pintype "passive"))
    )
    (net (code "48") (name "Net-(IC3-D)") (class "Default")
      (node (ref "IC3") (pin "3") (pinfunction "D_3") (pintype "passive"))
      (node (ref "Q18") (pin "3") (pinfunction "D_3") (pintype "passive"))
      (node (ref "R64") (pin "1") (pinfunction "1_1") (pintype "passive"))
    )
    (net (code "49") (name "Net-(IC3-LE)") (class "Default")
      (node (ref "IC3") (pin "1") (pinfunction "LE_1") (pintype "passive"))
      (node (ref "U16") (pin "4") (pinfunction "Y_4") (pintype "passive"))
    )
    (net (code "50") (name "Net-(IC4-LE)") (class "Default")
      (node (ref "IC4") (pin "1") (pinfunction "LE_1") (pintype "passive"))
      (node (ref "U17") (pin "4") (pinfunction "Y_4") (pintype "passive"))
    )
    (net (code "51") (name "Net-(Q3-D)") (class "Default")
      (node (ref "Q3") (pin "3") (pinfunction "D_3") (pintype "passive"))
      (node (ref "Q4") (pin "1") (pinfunction "G_1") (pintype "passive"))
      (node (ref "R26") (pin "1") (pinfunction "1_1") (pintype "passive"))
    )
    (net (code "52") (name "Net-(Q6-D)") (class "Default")
      (node (ref "Q6") (pin "3") (pinfunction "D_3") (pintype "passive"))
      (node (ref "Q7") (pin "1") (pinfunction "G_1") (pintype "passive"))
      (node (ref "R32") (pin "1") (pinfunction "1_1") (pintype "passive"))
    )
    (net (code "53") (name "Net-(Q10-G)") (class "Default")
      (node (ref "Q10") (pin "1") (pinfunction "G_1") (pintype "passive"))
      (node (ref "Q9") (pin "3") (pinfunction "D_3") (pintype "passive"))
      (node (ref "R38") (pin "1") (pinfunction "1_1") (pintype "passive"))
    )
    (net (code "54") (name "Net-(Q12-D)") (class "Default")
      (node (ref "Q12") (pin "3") (pinfunction "D_3") (pintype "passive"))
      (node (ref "Q13") (pin "1") (pinfunction "G_1") (pintype "passive"))
      (node (ref "R45") (pin "1") (pinfunction "1_1") (pintype "passive"))
    )
    (net (code "55") (name "Vdd") (class "Default")
      (node (ref "P5") (pin "1") (pinfunction "1_1") (pintype "passive"))
      (node (ref "P5") (pin "2") (pinfunction "2_2") (pintype "passive"))
      (node (ref "R24") (pin "2") (pinfunction "2_2") (pintype "passive"))
      (node (ref "R27") (pin "2") (pinfunction "2_2") (pintype "passive"))
      (node (ref "R30") (pin "2") (pinfunction "2_2") (pintype "passive"))
      (node (ref "R33") (pin "2") (pinfunction "2_2") (pintype "passive"))
      (node (ref "R36") (pin "2") (pinfunction "2_2") (pintype "passive"))
      (node (ref "R39") (pin "2") (pinfunction "2_2") (pintype "passive"))
      (node (ref "R43") (pin "2") (pinfunction "2_2") (pintype "passive"))
      (node (ref "R46") (pin "2") (pinfunction "2_2") (pintype "passive"))
    )
  )
)
